# schematic.net
KiCad netlist of a schematic drawn in EasyEDA
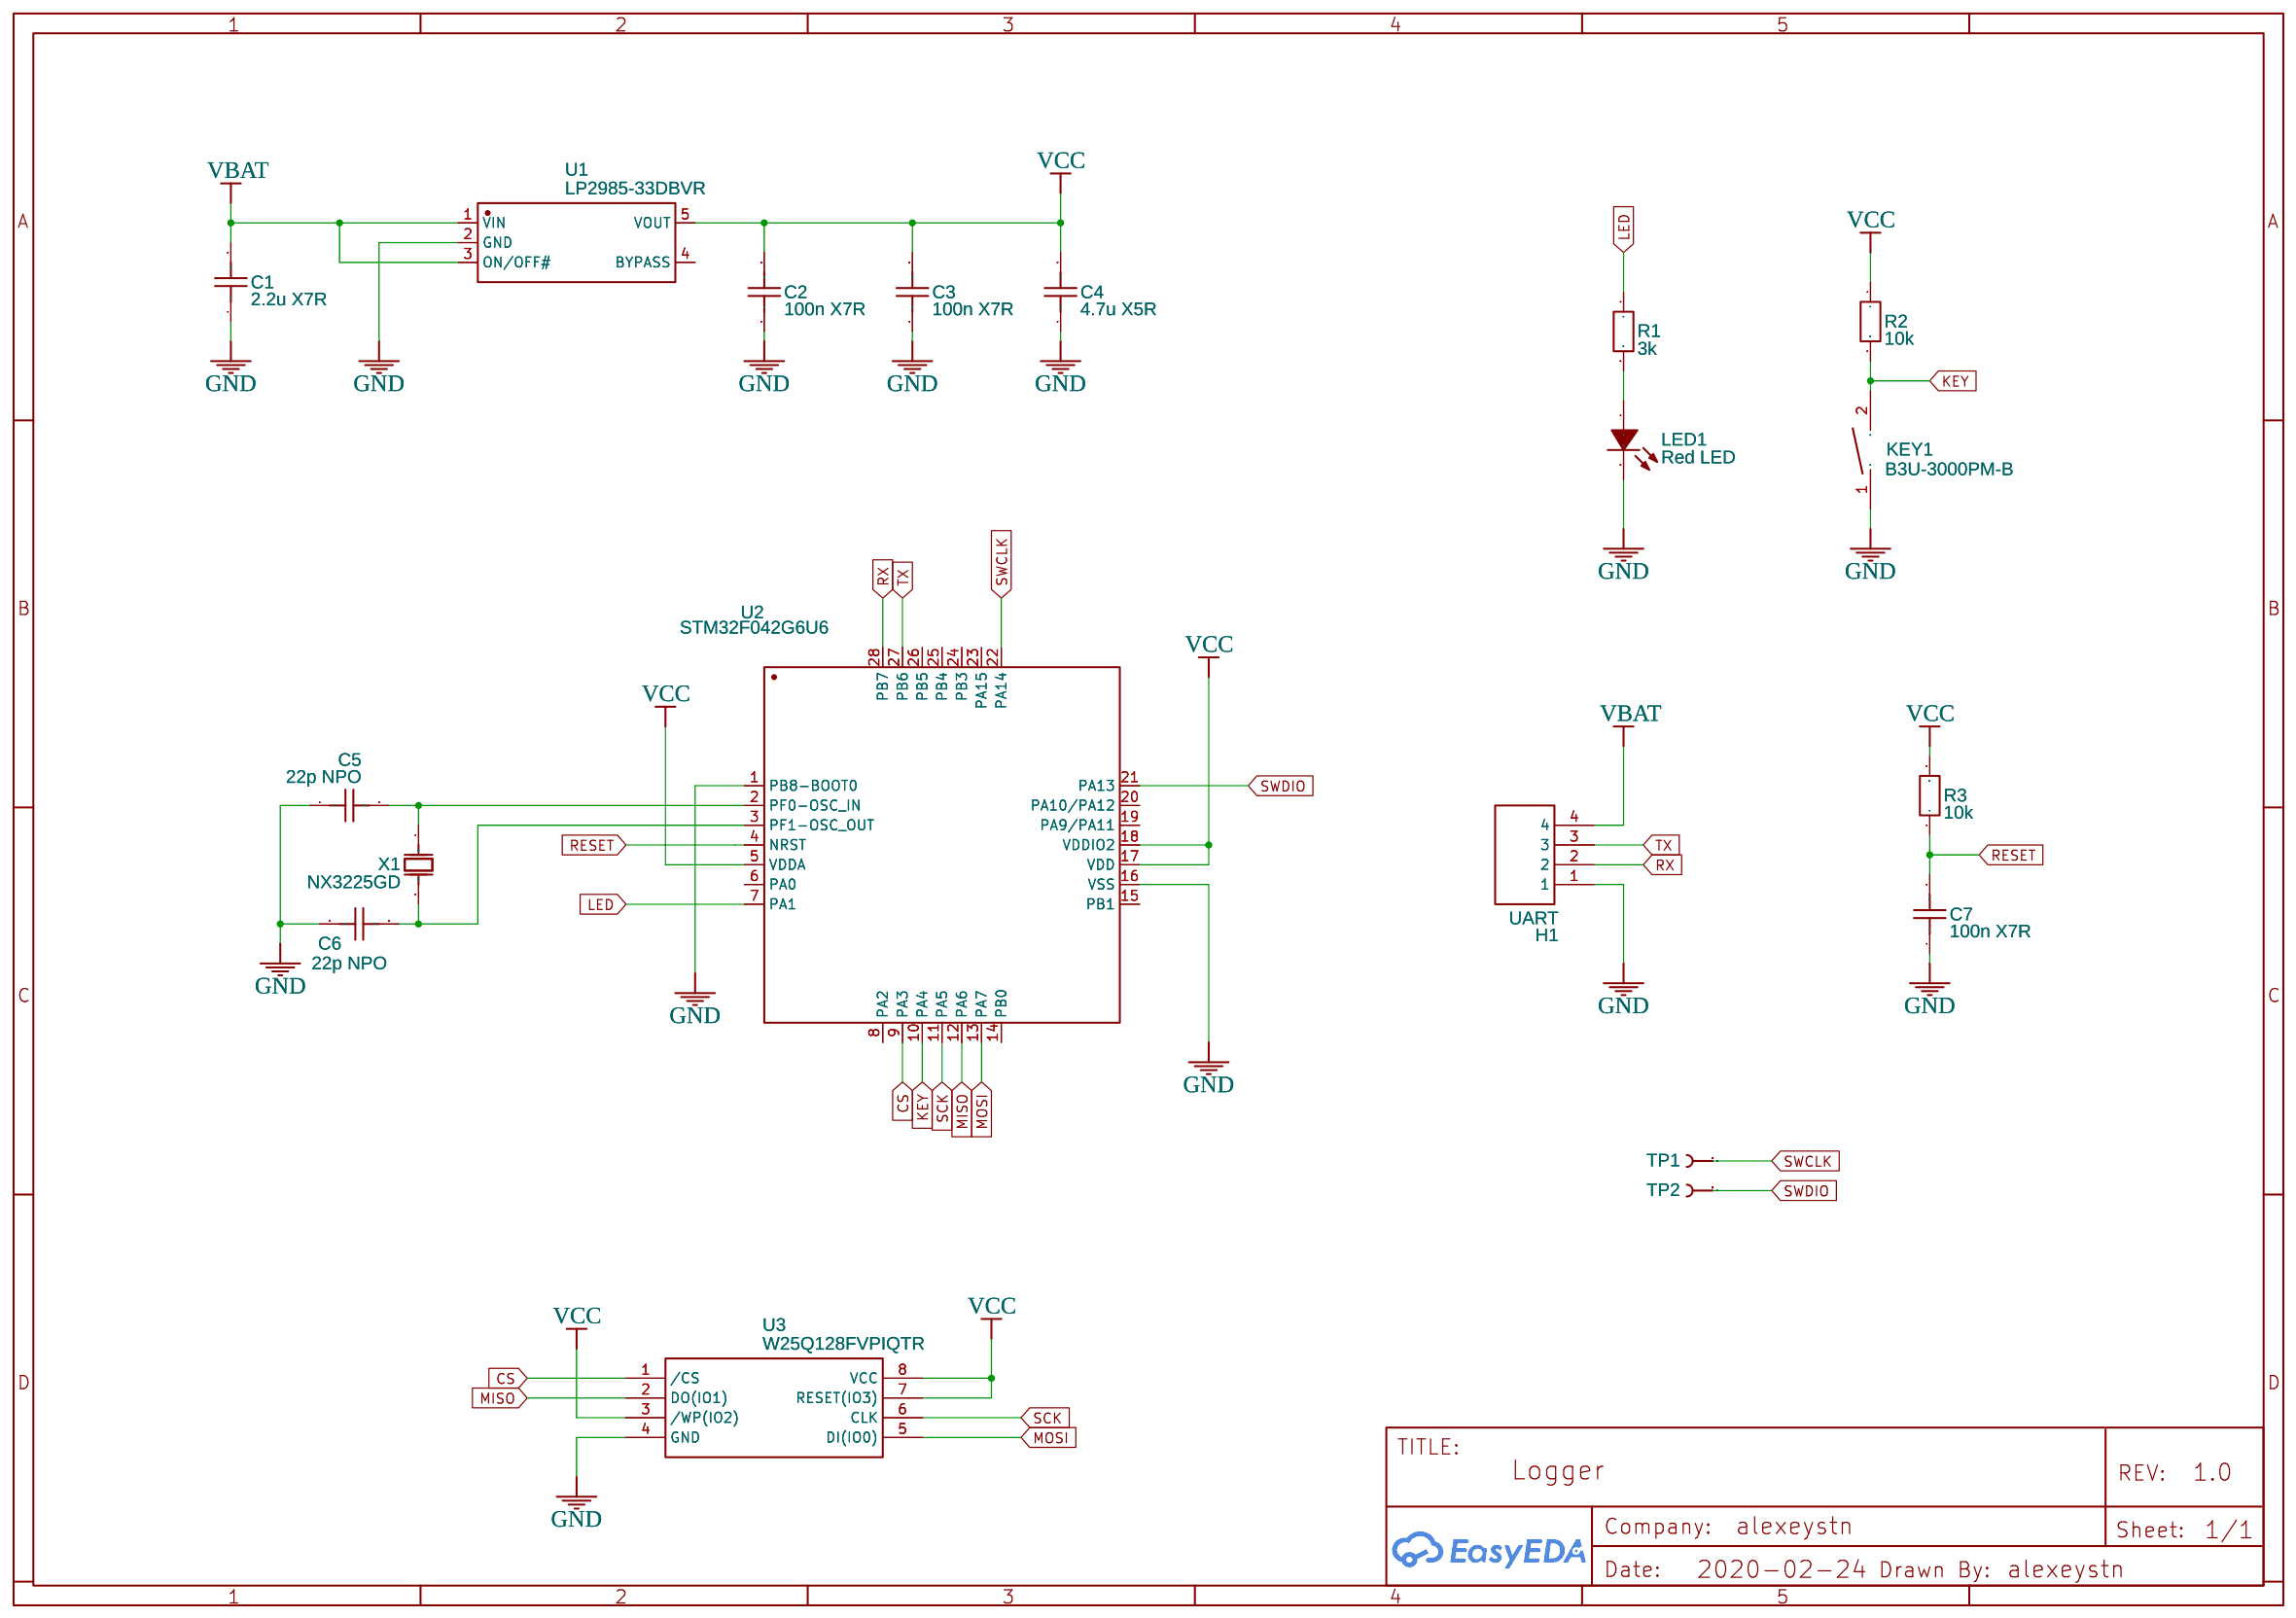
[diagram p0: schematic sheet]

(export (version "E")
  (design (tool "Eeschema 10.0.6"))
  (components
    (comp (ref "C1") (value "2.2u X7R") (libsource (lib "") (part "Cap_0805_US_1")))
    (comp (ref "C2") (value "100n X7R") (libsource (lib "") (part "Cap_0805_US_1")))
    (comp (ref "C3") (value "100n X7R") (libsource (lib "") (part "Cap_0805_US_1")))
    (comp (ref "C4") (value "4.7u X5R") (libsource (lib "") (part "Cap_0805_US_1")))
    (comp (ref "C5") (value "22p NPO") (libsource (lib "") (part "Cap_0805_US")))
    (comp (ref "C6") (value "22p NPO") (libsource (lib "") (part "Cap_0805_US")))
    (comp (ref "C7") (value "100n X7R") (libsource (lib "") (part "Cap_0805_US_1")))
    (comp (ref "H1")
      (value "UART")
      (fields
        (field (name "BOM_Manufacturer Part") "220S-1*4P H=8.5MM Ytype Gold-plated")
        (field (name "BOM_Supplier Part") "C124413")
      )
      (libsource (lib "") (part "220S-1*4P H=8.5MM Ytype Gold-plated"))
    )
    (comp (ref "KEY1")
      (value "B3U-3000PM-B")
      (fields (field (name "BOM_Supplier Part") "C306884"))
      (libsource (lib "") (part "B3U-3000PM-B"))
    )
    (comp (ref "LED1")
      (value "Red LED")
      (fields
        (field (name "BOM_Manufacturer Part") "17-21SURC/S530-A2/TR8")
        (field (name "BOM_Supplier Part") "C131244")
      )
      (libsource (lib "") (part "17-21SURC/S530-A2/TR8"))
    )
    (comp (ref "R1") (value "3k") (libsource (lib "") (part "Res_0805(1/8W)_EU_1")))
    (comp (ref "R2") (value "10k") (libsource (lib "") (part "Res_0805(1/8W)_EU_1")))
    (comp (ref "R3") (value "10k") (libsource (lib "") (part "Res_0805(1/8W)_EU")))
    (comp (ref "TP1") (value "TEST-POINT3") (libsource (lib "") (part "TEST-POINT3")))
    (comp (ref "TP2") (value "TEST-POINT3") (libsource (lib "") (part "TEST-POINT3")))
    (comp (ref "U1")
      (value "LP2985-33DBVR")
      (fields (field (name "BOM_Supplier Part") "C95414"))
      (libsource (lib "") (part "LP2985-33DBVR"))
    )
    (comp (ref "U2")
      (value "STM32F042G6U6")
      (fields
        (field (name "BOM_Manufacturer Part") "STM32F042G4U6")
        (field (name "BOM_Supplier Part") "C88048")
      )
      (libsource (lib "") (part "STM32F042G4U6"))
    )
    (comp (ref "U3")
      (value "W25Q128FVPIQTR")
      (fields (field (name "BOM_Supplier Part") "C89387"))
      (libsource (lib "") (part "W25Q128FVPIQTR"))
    )
    (comp (ref "X1") (value "NX3225GD") (libsource (lib "") (part "NX3225GD-8MHZ-STD-CRA-3")))
  )
  (nets
    (net (code "1") (name "CS") (class "Default")
      (node (ref "U2") (pin "9") (pinfunction "PA3_9") (pintype "unspecified"))
      (node (ref "U3") (pin "1") (pinfunction "/CS_1") (pintype "unspecified"))
    )
    (net (code "2") (name "GND") (class "Default")
      (node (ref "C1") (pin "1") (pinfunction "1_1") (pintype "unspecified"))
      (node (ref "C2") (pin "1") (pinfunction "1_1") (pintype "unspecified"))
      (node (ref "C3") (pin "1") (pinfunction "1_1") (pintype "unspecified"))
      (node (ref "C4") (pin "1") (pinfunction "1_1") (pintype "unspecified"))
      (node (ref "C5") (pin "1") (pinfunction "1_1") (pintype "unspecified"))
      (node (ref "C6") (pin "1") (pinfunction "1_1") (pintype "unspecified"))
      (node (ref "C7") (pin "1") (pinfunction "1_1") (pintype "unspecified"))
      (node (ref "H1") (pin "1") (pinfunction "1_1") (pintype "unspecified"))
      (node (ref "KEY1") (pin "1") (pinfunction "1_1") (pintype "input"))
      (node (ref "LED1") (pin "2") (pinfunction "K_2") (pintype "unspecified"))
      (node (ref "U1") (pin "2") (pinfunction "GND_2") (pintype "unspecified"))
      (node (ref "U2") (pin "1") (pinfunction "PB8-BOOT0_1") (pintype "unspecified"))
      (node (ref "U2") (pin "16") (pinfunction "VSS_16") (pintype "unspecified"))
      (node (ref "U3") (pin "4") (pinfunction "GND_4") (pintype "unspecified"))
    )
    (net (code "3") (name "KEY") (class "Default")
      (node (ref "KEY1") (pin "2") (pinfunction "2_2") (pintype "input"))
      (node (ref "R2") (pin "2") (pinfunction "2_2") (pintype "unspecified"))
      (node (ref "U2") (pin "10") (pinfunction "PA4_10") (pintype "unspecified"))
    )
    (net (code "4") (name "LED") (class "Default")
      (node (ref "R1") (pin "1") (pinfunction "1_1") (pintype "unspecified"))
      (node (ref "U2") (pin "7") (pinfunction "PA1_7") (pintype "unspecified"))
    )
    (net (code "5") (name "MISO") (class "Default")
      (node (ref "U2") (pin "12") (pinfunction "PA6_12") (pintype "unspecified"))
      (node (ref "U3") (pin "2") (pinfunction "DO(IO1)_2") (pintype "unspecified"))
    )
    (net (code "6") (name "MOSI") (class "Default")
      (node (ref "U2") (pin "13") (pinfunction "PA7_13") (pintype "unspecified"))
      (node (ref "U3") (pin "5") (pinfunction "DI(IO0)_5") (pintype "unspecified"))
    )
    (net (code "7") (name "Net-(LED1-A)") (class "Default")
      (node (ref "LED1") (pin "1") (pinfunction "A_1") (pintype "unspecified"))
      (node (ref "R1") (pin "2") (pinfunction "2_2") (pintype "unspecified"))
    )
    (net (code "8") (name "Net-(U2-PF0-OSC_IN)") (class "Default")
      (node (ref "C5") (pin "2") (pinfunction "2_2") (pintype "unspecified"))
      (node (ref "U2") (pin "2") (pinfunction "PF0-OSC_IN_2") (pintype "unspecified"))
      (node (ref "X1") (pin "1") (pinfunction "OSC1_1") (pintype "input"))
    )
    (net (code "9") (name "Net-(U2-PF1-OSC_OUT)") (class "Default")
      (node (ref "C6") (pin "2") (pinfunction "2_2") (pintype "unspecified"))
      (node (ref "U2") (pin "3") (pinfunction "PF1-OSC_OUT_3") (pintype "unspecified"))
      (node (ref "X1") (pin "2") (pinfunction "OSC2_2") (pintype "input"))
    )
    (net (code "10") (name "RESET") (class "Default")
      (node (ref "C7") (pin "2") (pinfunction "2_2") (pintype "unspecified"))
      (node (ref "R3") (pin "1") (pinfunction "1_1") (pintype "unspecified"))
      (node (ref "U2") (pin "4") (pinfunction "NRST_4") (pintype "unspecified"))
    )
    (net (code "11") (name "RX") (class "Default")
      (node (ref "H1") (pin "2") (pinfunction "2_2") (pintype "unspecified"))
      (node (ref "U2") (pin "28") (pinfunction "PB7_28") (pintype "unspecified"))
    )
    (net (code "12") (name "SCK") (class "Default")
      (node (ref "U2") (pin "11") (pinfunction "PA5_11") (pintype "unspecified"))
      (node (ref "U3") (pin "6") (pinfunction "CLK_6") (pintype "unspecified"))
    )
    (net (code "13") (name "SWCLK") (class "Default")
      (node (ref "TP1") (pin "P$1") (pinfunction "1_P$1") (pintype "unspecified"))
      (node (ref "U2") (pin "22") (pinfunction "PA14_22") (pintype "unspecified"))
    )
    (net (code "14") (name "SWDIO") (class "Default")
      (node (ref "TP2") (pin "P$1") (pinfunction "1_P$1") (pintype "unspecified"))
      (node (ref "U2") (pin "21") (pinfunction "PA13_21") (pintype "unspecified"))
    )
    (net (code "15") (name "TX") (class "Default")
      (node (ref "H1") (pin "3") (pinfunction "3_3") (pintype "unspecified"))
      (node (ref "U2") (pin "27") (pinfunction "PB6_27") (pintype "unspecified"))
    )
    (net (code "16") (name "VBAT") (class "Default")
      (node (ref "C1") (pin "2") (pinfunction "2_2") (pintype "unspecified"))
      (node (ref "H1") (pin "4") (pinfunction "4_4") (pintype "unspecified"))
      (node (ref "U1") (pin "1") (pinfunction "VIN_1") (pintype "unspecified"))
      (node (ref "U1") (pin "3") (pinfunction "ON/OFF#_3") (pintype "unspecified"))
    )
    (net (code "17") (name "VCC") (class "Default")
      (node (ref "C2") (pin "2") (pinfunction "2_2") (pintype "unspecified"))
      (node (ref "C3") (pin "2") (pinfunction "2_2") (pintype "unspecified"))
      (node (ref "C4") (pin "2") (pinfunction "2_2") (pintype "unspecified"))
      (node (ref "R2") (pin "1") (pinfunction "1_1") (pintype "unspecified"))
      (node (ref "R3") (pin "2") (pinfunction "2_2") (pintype "unspecified"))
      (node (ref "U1") (pin "5") (pinfunction "VOUT_5") (pintype "unspecified"))
      (node (ref "U2") (pin "17") (pinfunction "VDD_17") (pintype "unspecified"))
      (node (ref "U2") (pin "18") (pinfunction "VDDIO2_18") (pintype "unspecified"))
      (node (ref "U2") (pin "5") (pinfunction "VDDA_5") (pintype "unspecified"))
      (node (ref "U3") (pin "3") (pinfunction "/WP(IO2)_3") (pintype "unspecified"))
      (node (ref "U3") (pin "7") (pinfunction "RESET(IO3)_7") (pintype "unspecified"))
      (node (ref "U3") (pin "8") (pinfunction "VCC_8") (pintype "unspecified"))
    )
    (net (code "18") (name "unconnected-(U1-BYPASS-Pad4)") (class "Default")
      (node (ref "U1") (pin "4") (pinfunction "BYPASS_4") (pintype "unspecified"))
    )
    (net (code "19") (name "unconnected-(U2-PA0-Pad6)") (class "Default")
      (node (ref "U2") (pin "6") (pinfunction "PA0_6") (pintype "unspecified"))
    )
    (net (code "20") (name "unconnected-(U2-PA2-Pad8)") (class "Default")
      (node (ref "U2") (pin "8") (pinfunction "PA2_8") (pintype "unspecified"))
    )
    (net (code "21") (name "unconnected-(U2-PA9{slash}PA11-Pad19)") (class "Default")
      (node (ref "U2") (pin "19") (pinfunction "PA9/PA11_19") (pintype "unspecified"))
    )
    (net (code "22") (name "unconnected-(U2-PA10{slash}PA12-Pad20)") (class "Default")
      (node (ref "U2") (pin "20") (pinfunction "PA10/PA12_20") (pintype "unspecified"))
    )
    (net (code "23") (name "unconnected-(U2-PA15-Pad23)") (class "Default")
      (node (ref "U2") (pin "23") (pinfunction "PA15_23") (pintype "unspecified"))
    )
    (net (code "24") (name "unconnected-(U2-PB0-Pad14)") (class "Default")
      (node (ref "U2") (pin "14") (pinfunction "PB0_14") (pintype "unspecified"))
    )
    (net (code "25") (name "unconnected-(U2-PB1-Pad15)") (class "Default")
      (node (ref "U2") (pin "15") (pinfunction "PB1_15") (pintype "unspecified"))
    )
    (net (code "26") (name "unconnected-(U2-PB3-Pad24)") (class "Default")
      (node (ref "U2") (pin "24") (pinfunction "PB3_24") (pintype "unspecified"))
    )
    (net (code "27") (name "unconnected-(U2-PB4-Pad25)") (class "Default")
      (node (ref "U2") (pin "25") (pinfunction "PB4_25") (pintype "unspecified"))
    )
    (net (code "28") (name "unconnected-(U2-PB5-Pad26)") (class "Default")
      (node (ref "U2") (pin "26") (pinfunction "PB5_26") (pintype "unspecified"))
    )
  )
)
